# Beating_Heart.net
KiCad netlist of a schematic drawn in EAGLE
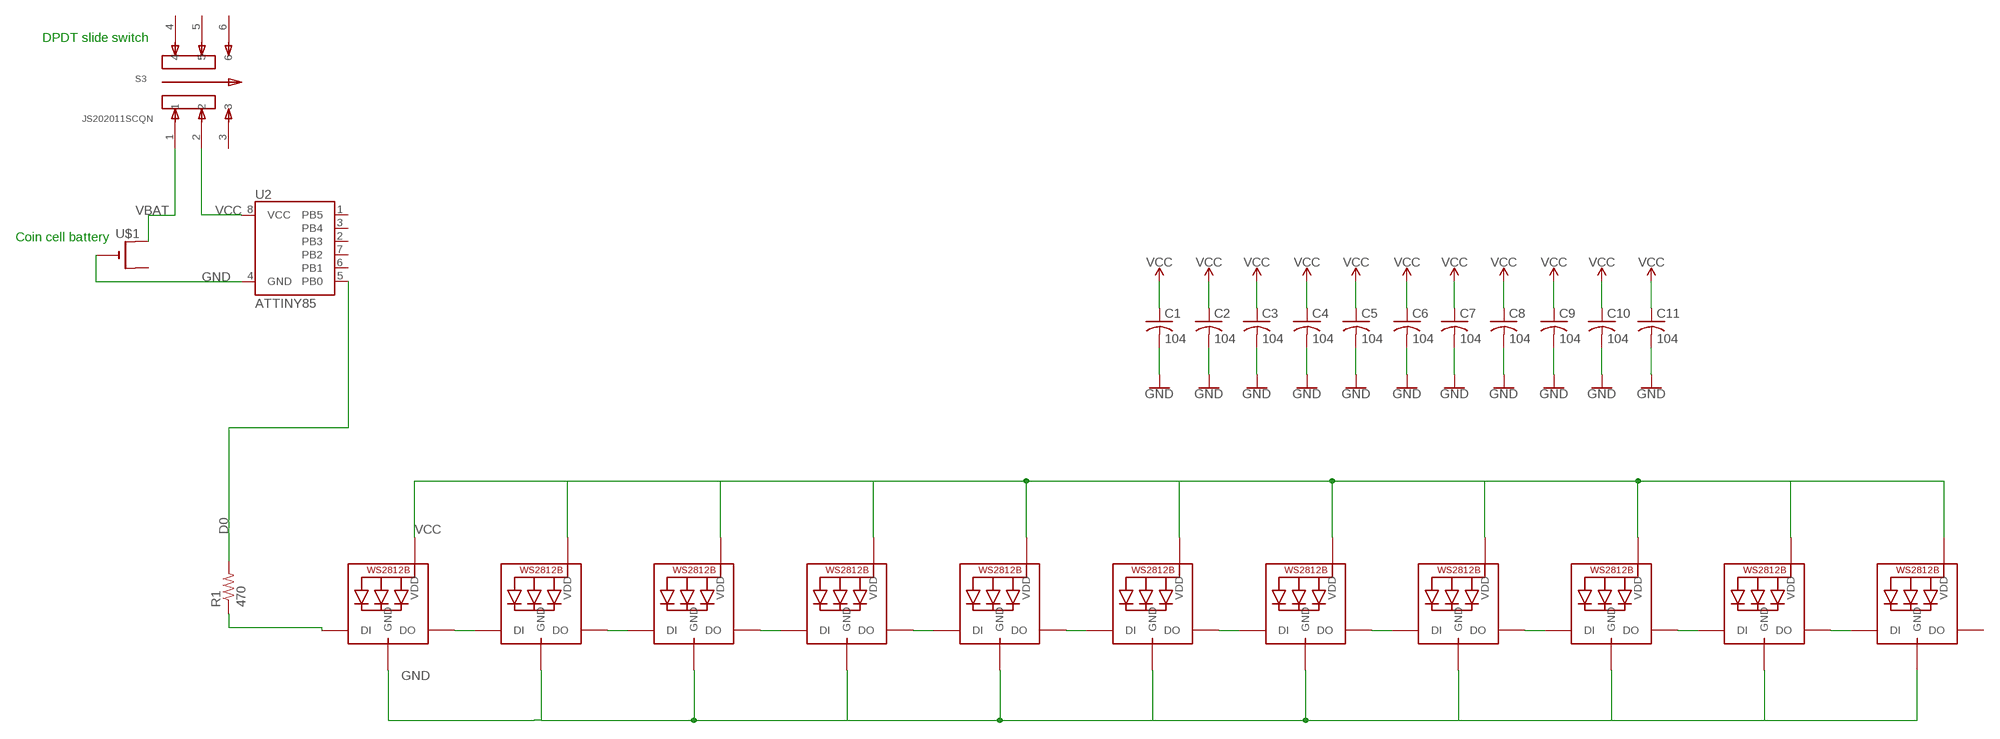
[diagram p0: schematic, sheet 1]

(export (version "E")
  (design (tool "Eeschema 10.0.6"))
  (components
    (comp (ref "C1")
      (value "104")
      (footprint "eagle-import:C0805K")
      (libsource (lib "eagle-import") (part "C-USC0805K"))
    )
    (comp (ref "C2")
      (value "104")
      (footprint "eagle-import:C0805K")
      (libsource (lib "eagle-import") (part "C-USC0805K"))
    )
    (comp (ref "C3")
      (value "104")
      (footprint "eagle-import:C0805K")
      (libsource (lib "eagle-import") (part "C-USC0805K"))
    )
    (comp (ref "C4")
      (value "104")
      (footprint "eagle-import:C0805K")
      (libsource (lib "eagle-import") (part "C-USC0805K"))
    )
    (comp (ref "C5")
      (value "104")
      (footprint "eagle-import:C0805K")
      (libsource (lib "eagle-import") (part "C-USC0805K"))
    )
    (comp (ref "C6")
      (value "104")
      (footprint "eagle-import:C0805K")
      (libsource (lib "eagle-import") (part "C-USC0805K"))
    )
    (comp (ref "C7")
      (value "104")
      (footprint "eagle-import:C0805K")
      (libsource (lib "eagle-import") (part "C-USC0805K"))
    )
    (comp (ref "C8")
      (value "104")
      (footprint "eagle-import:C0805K")
      (libsource (lib "eagle-import") (part "C-USC0805K"))
    )
    (comp (ref "C9")
      (value "104")
      (footprint "eagle-import:C0805K")
      (libsource (lib "eagle-import") (part "C-USC0805K"))
    )
    (comp (ref "C10")
      (value "104")
      (footprint "eagle-import:C0805K")
      (libsource (lib "eagle-import") (part "C-USC0805K"))
    )
    (comp (ref "C11")
      (value "104")
      (footprint "eagle-import:C0805K")
      (libsource (lib "eagle-import") (part "C-USC0805K"))
    )
    (comp (ref "LED1")
      (value "WS2812B5050")
      (footprint "eagle-import:WS2812B")
      (libsource (lib "eagle-import") (part "WS2812B5050"))
    )
    (comp (ref "LED2")
      (value "WS2812B5050")
      (footprint "eagle-import:WS2812B")
      (libsource (lib "eagle-import") (part "WS2812B5050"))
    )
    (comp (ref "LED3")
      (value "WS2812B5050")
      (footprint "eagle-import:WS2812B")
      (libsource (lib "eagle-import") (part "WS2812B5050"))
    )
    (comp (ref "LED4")
      (value "WS2812B5050")
      (footprint "eagle-import:WS2812B")
      (libsource (lib "eagle-import") (part "WS2812B5050"))
    )
    (comp (ref "LED5")
      (value "WS2812B5050")
      (footprint "eagle-import:WS2812B")
      (libsource (lib "eagle-import") (part "WS2812B5050"))
    )
    (comp (ref "LED6")
      (value "WS2812B5050")
      (footprint "eagle-import:WS2812B")
      (libsource (lib "eagle-import") (part "WS2812B5050"))
    )
    (comp (ref "LED7")
      (value "WS2812B5050")
      (footprint "eagle-import:WS2812B")
      (libsource (lib "eagle-import") (part "WS2812B5050"))
    )
    (comp (ref "LED8")
      (value "WS2812B5050")
      (footprint "eagle-import:WS2812B")
      (libsource (lib "eagle-import") (part "WS2812B5050"))
    )
    (comp (ref "LED9")
      (value "WS2812B5050")
      (footprint "eagle-import:WS2812B")
      (libsource (lib "eagle-import") (part "WS2812B5050"))
    )
    (comp (ref "LED10")
      (value "WS2812B5050")
      (footprint "eagle-import:WS2812B")
      (libsource (lib "eagle-import") (part "WS2812B5050"))
    )
    (comp (ref "LED11")
      (value "WS2812B5050")
      (footprint "eagle-import:WS2812B")
      (libsource (lib "eagle-import") (part "WS2812B5050"))
    )
    (comp (ref "R1")
      (value "470")
      (footprint "eagle-import:M0805")
      (libsource (lib "eagle-import") (part "R-US_M0805"))
    )
    (comp (ref "S3")
      (value "JS202011SCQN")
      (footprint "eagle-import:SW_JS202011SCQN")
      (fields (field (name "DIGI-KEY_PART_NUMBER") "401-2002-1-ND") (field (name "MF") "C&K"))
      (libsource (lib "eagle-import") (part "JS202011SCQN"))
    )
    (comp (ref "U$1")
      (value "CR1220SMT")
      (footprint "eagle-import:CR1220-SMD")
      (libsource (lib "eagle-import") (part "CR1220SMT"))
    )
    (comp (ref "U2")
      (value "ATTINY85")
      (footprint "eagle-import:ATTINY85")
      (libsource (lib "eagle-import") (part "ATTINY85"))
    )
  )
  (nets
    (net (code "1") (name "/D0") (class "Default")
      (node (ref "R1") (pin "2") (pinfunction "2_2") (pintype "passive"))
      (node (ref "U2") (pin "5") (pinfunction "PB0_5") (pintype "bidirectional"))
    )
    (net (code "2") (name "/VBAT") (class "Default")
      (node (ref "S3") (pin "1") (pinfunction "1_1") (pintype "passive"))
      (node (ref "U$1") (pin "+$1") (pinfunction "+_+$1") (pintype "passive"))
    )
    (net (code "3") (name "GND") (class "Default")
      (node (ref "C1") (pin "2") (pinfunction "2_2") (pintype "passive"))
      (node (ref "C10") (pin "2") (pinfunction "2_2") (pintype "passive"))
      (node (ref "C11") (pin "2") (pinfunction "2_2") (pintype "passive"))
      (node (ref "C2") (pin "2") (pinfunction "2_2") (pintype "passive"))
      (node (ref "C3") (pin "2") (pinfunction "2_2") (pintype "passive"))
      (node (ref "C4") (pin "2") (pinfunction "2_2") (pintype "passive"))
      (node (ref "C5") (pin "2") (pinfunction "2_2") (pintype "passive"))
      (node (ref "C6") (pin "2") (pinfunction "2_2") (pintype "passive"))
      (node (ref "C7") (pin "2") (pinfunction "2_2") (pintype "passive"))
      (node (ref "C8") (pin "2") (pinfunction "2_2") (pintype "passive"))
      (node (ref "C9") (pin "2") (pinfunction "2_2") (pintype "passive"))
      (node (ref "LED1") (pin "3-GND") (pinfunction "GND_3-GND") (pintype "power_in"))
      (node (ref "LED10") (pin "3-GND") (pinfunction "GND_3-GND") (pintype "power_in"))
      (node (ref "LED11") (pin "3-GND") (pinfunction "GND_3-GND") (pintype "power_in"))
      (node (ref "LED2") (pin "3-GND") (pinfunction "GND_3-GND") (pintype "power_in"))
      (node (ref "LED3") (pin "3-GND") (pinfunction "GND_3-GND") (pintype "power_in"))
      (node (ref "LED4") (pin "3-GND") (pinfunction "GND_3-GND") (pintype "power_in"))
      (node (ref "LED5") (pin "3-GND") (pinfunction "GND_3-GND") (pintype "power_in"))
      (node (ref "LED6") (pin "3-GND") (pinfunction "GND_3-GND") (pintype "power_in"))
      (node (ref "LED7") (pin "3-GND") (pinfunction "GND_3-GND") (pintype "power_in"))
      (node (ref "LED8") (pin "3-GND") (pinfunction "GND_3-GND") (pintype "power_in"))
      (node (ref "LED9") (pin "3-GND") (pinfunction "GND_3-GND") (pintype "power_in"))
      (node (ref "U$1") (pin "-") (pinfunction "-_-") (pintype "passive"))
      (node (ref "U2") (pin "4") (pinfunction "GND_4") (pintype "bidirectional"))
    )
    (net (code "4") (name "Net-(LED1-DI)") (class "Default")
      (node (ref "LED1") (pin "4-DIN") (pinfunction "DI_4-DIN") (pintype "input"))
      (node (ref "R1") (pin "1") (pinfunction "1_1") (pintype "passive"))
    )
    (net (code "5") (name "Net-(LED1-DO)") (class "Default")
      (node (ref "LED1") (pin "2-DOUT") (pinfunction "DO_2-DOUT") (pintype "output"))
      (node (ref "LED2") (pin "4-DIN") (pinfunction "DI_4-DIN") (pintype "input"))
    )
    (net (code "6") (name "Net-(LED2-DO)") (class "Default")
      (node (ref "LED2") (pin "2-DOUT") (pinfunction "DO_2-DOUT") (pintype "output"))
      (node (ref "LED3") (pin "4-DIN") (pinfunction "DI_4-DIN") (pintype "input"))
    )
    (net (code "7") (name "Net-(LED3-DO)") (class "Default")
      (node (ref "LED3") (pin "2-DOUT") (pinfunction "DO_2-DOUT") (pintype "output"))
      (node (ref "LED4") (pin "4-DIN") (pinfunction "DI_4-DIN") (pintype "input"))
    )
    (net (code "8") (name "Net-(LED4-DO)") (class "Default")
      (node (ref "LED4") (pin "2-DOUT") (pinfunction "DO_2-DOUT") (pintype "output"))
      (node (ref "LED5") (pin "4-DIN") (pinfunction "DI_4-DIN") (pintype "input"))
    )
    (net (code "9") (name "Net-(LED5-DO)") (class "Default")
      (node (ref "LED5") (pin "2-DOUT") (pinfunction "DO_2-DOUT") (pintype "output"))
      (node (ref "LED6") (pin "4-DIN") (pinfunction "DI_4-DIN") (pintype "input"))
    )
    (net (code "10") (name "Net-(LED6-DO)") (class "Default")
      (node (ref "LED6") (pin "2-DOUT") (pinfunction "DO_2-DOUT") (pintype "output"))
      (node (ref "LED7") (pin "4-DIN") (pinfunction "DI_4-DIN") (pintype "input"))
    )
    (net (code "11") (name "Net-(LED7-DO)") (class "Default")
      (node (ref "LED7") (pin "2-DOUT") (pinfunction "DO_2-DOUT") (pintype "output"))
      (node (ref "LED8") (pin "4-DIN") (pinfunction "DI_4-DIN") (pintype "input"))
    )
    (net (code "12") (name "Net-(LED8-DO)") (class "Default")
      (node (ref "LED8") (pin "2-DOUT") (pinfunction "DO_2-DOUT") (pintype "output"))
      (node (ref "LED9") (pin "4-DIN") (pinfunction "DI_4-DIN") (pintype "input"))
    )
    (net (code "13") (name "Net-(LED10-DI)") (class "Default")
      (node (ref "LED10") (pin "4-DIN") (pinfunction "DI_4-DIN") (pintype "input"))
      (node (ref "LED9") (pin "2-DOUT") (pinfunction "DO_2-DOUT") (pintype "output"))
    )
    (net (code "14") (name "Net-(LED10-DO)") (class "Default")
      (node (ref "LED10") (pin "2-DOUT") (pinfunction "DO_2-DOUT") (pintype "output"))
      (node (ref "LED11") (pin "4-DIN") (pinfunction "DI_4-DIN") (pintype "input"))
    )
    (net (code "15") (name "VCC") (class "Default")
      (node (ref "C1") (pin "1") (pinfunction "1_1") (pintype "passive"))
      (node (ref "C10") (pin "1") (pinfunction "1_1") (pintype "passive"))
      (node (ref "C11") (pin "1") (pinfunction "1_1") (pintype "passive"))
      (node (ref "C2") (pin "1") (pinfunction "1_1") (pintype "passive"))
      (node (ref "C3") (pin "1") (pinfunction "1_1") (pintype "passive"))
      (node (ref "C4") (pin "1") (pinfunction "1_1") (pintype "passive"))
      (node (ref "C5") (pin "1") (pinfunction "1_1") (pintype "passive"))
      (node (ref "C6") (pin "1") (pinfunction "1_1") (pintype "passive"))
      (node (ref "C7") (pin "1") (pinfunction "1_1") (pintype "passive"))
      (node (ref "C8") (pin "1") (pinfunction "1_1") (pintype "passive"))
      (node (ref "C9") (pin "1") (pinfunction "1_1") (pintype "passive"))
      (node (ref "LED1") (pin "1-VDD") (pinfunction "VDD_1-VDD") (pintype "power_in"))
      (node (ref "LED10") (pin "1-VDD") (pinfunction "VDD_1-VDD") (pintype "power_in"))
      (node (ref "LED11") (pin "1-VDD") (pinfunction "VDD_1-VDD") (pintype "power_in"))
      (node (ref "LED2") (pin "1-VDD") (pinfunction "VDD_1-VDD") (pintype "power_in"))
      (node (ref "LED3") (pin "1-VDD") (pinfunction "VDD_1-VDD") (pintype "power_in"))
      (node (ref "LED4") (pin "1-VDD") (pinfunction "VDD_1-VDD") (pintype "power_in"))
      (node (ref "LED5") (pin "1-VDD") (pinfunction "VDD_1-VDD") (pintype "power_in"))
      (node (ref "LED6") (pin "1-VDD") (pinfunction "VDD_1-VDD") (pintype "power_in"))
      (node (ref "LED7") (pin "1-VDD") (pinfunction "VDD_1-VDD") (pintype "power_in"))
      (node (ref "LED8") (pin "1-VDD") (pinfunction "VDD_1-VDD") (pintype "power_in"))
      (node (ref "LED9") (pin "1-VDD") (pinfunction "VDD_1-VDD") (pintype "power_in"))
      (node (ref "S3") (pin "2") (pinfunction "2_2") (pintype "passive"))
      (node (ref "U2") (pin "8") (pinfunction "VCC_8") (pintype "bidirectional"))
    )
    (net (code "16") (name "unconnected-(LED11-DO-Pad2-DOUT)") (class "Default")
      (node (ref "LED11") (pin "2-DOUT") (pinfunction "DO_2-DOUT") (pintype "output"))
    )
    (net (code "17") (name "unconnected-(S3-Pad3)") (class "Default")
      (node (ref "S3") (pin "3") (pinfunction "3_3") (pintype "passive"))
    )
    (net (code "18") (name "unconnected-(S3-Pad4)") (class "Default")
      (node (ref "S3") (pin "4") (pinfunction "4_4") (pintype "passive"))
    )
    (net (code "19") (name "unconnected-(S3-Pad5)") (class "Default")
      (node (ref "S3") (pin "5") (pinfunction "5_5") (pintype "passive"))
    )
    (net (code "20") (name "unconnected-(S3-Pad6)") (class "Default")
      (node (ref "S3") (pin "6") (pinfunction "6_6") (pintype "passive"))
    )
    (net (code "21") (name "unconnected-(U$1-+1-Pad+$2)") (class "Default")
      (node (ref "U$1") (pin "+$2") (pinfunction "+1_+$2") (pintype "passive"))
    )
    (net (code "22") (name "unconnected-(U2-PB1-Pad6)") (class "Default")
      (node (ref "U2") (pin "6") (pinfunction "PB1_6") (pintype "bidirectional"))
    )
    (net (code "23") (name "unconnected-(U2-PB2-Pad7)") (class "Default")
      (node (ref "U2") (pin "7") (pinfunction "PB2_7") (pintype "bidirectional"))
    )
    (net (code "24") (name "unconnected-(U2-PB3-Pad2)") (class "Default")
      (node (ref "U2") (pin "2") (pinfunction "PB3_2") (pintype "bidirectional"))
    )
    (net (code "25") (name "unconnected-(U2-PB4-Pad3)") (class "Default")
      (node (ref "U2") (pin "3") (pinfunction "PB4_3") (pintype "bidirectional"))
    )
    (net (code "26") (name "unconnected-(U2-PB5-Pad1)") (class "Default")
      (node (ref "U2") (pin "1") (pinfunction "PB5_1") (pintype "bidirectional"))
    )
  )
)
